# RWcircuit_2.net
KiCad netlist of a schematic drawn in Altium Designer
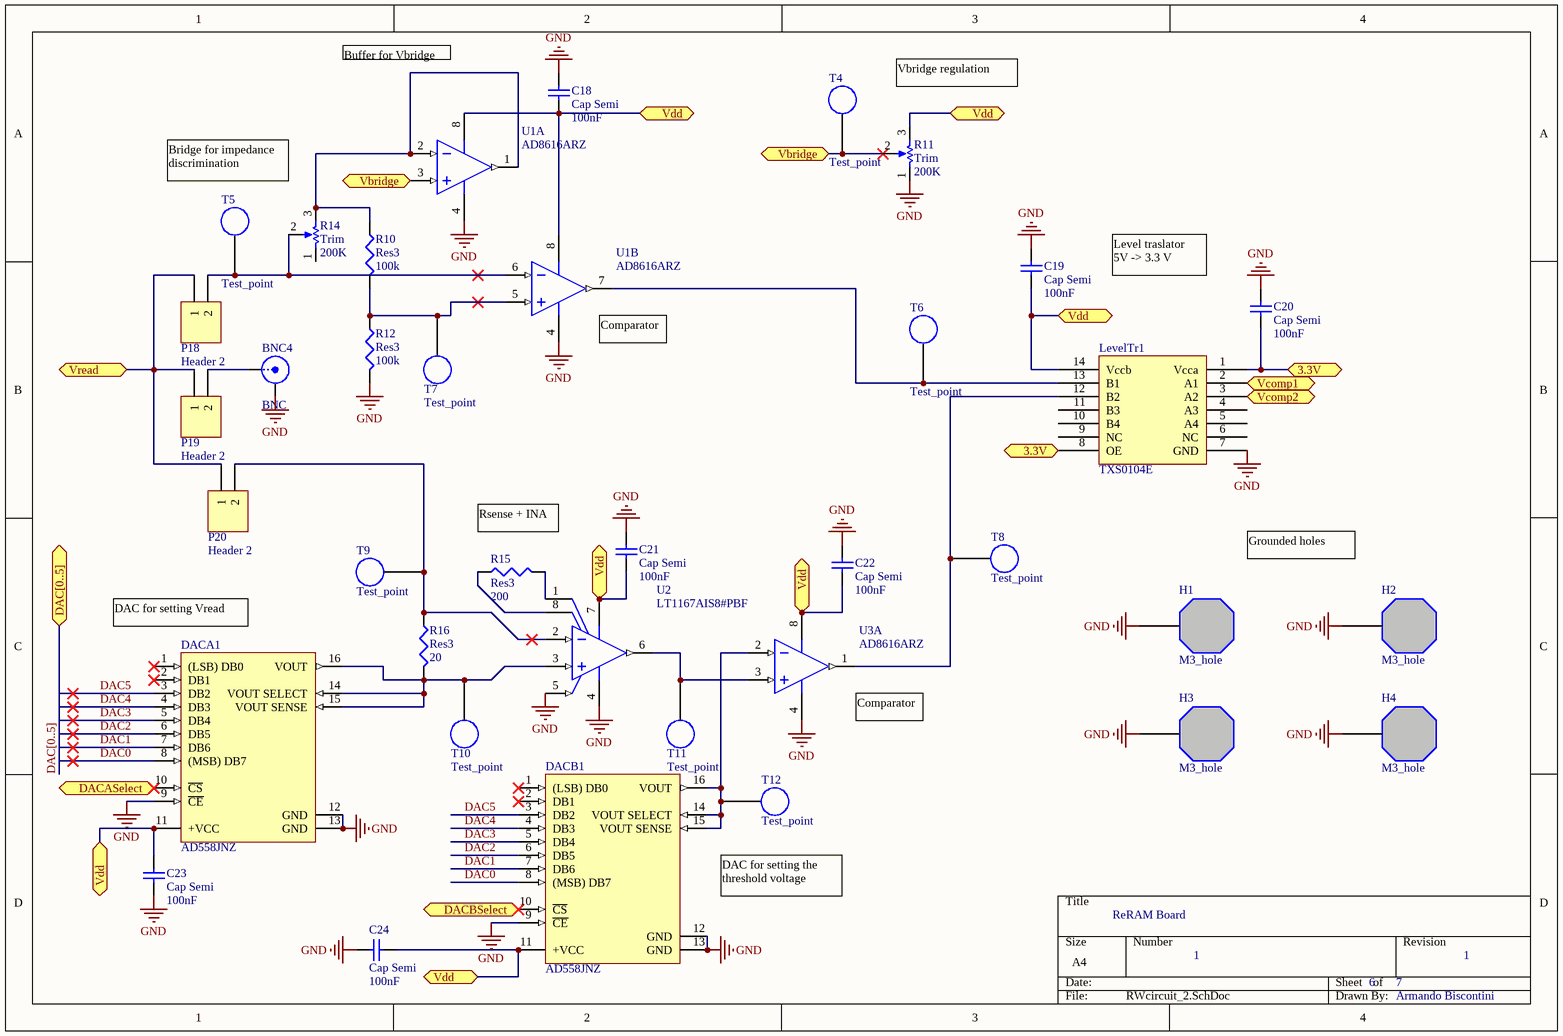
[diagram p0: RWcircuit_2.SchDoc]

(export (version "E")
  (design (tool "Eeschema 10.0.6"))
  (components
    (comp (ref "BNC4")
      (value "BNC")
      (footprint "BNC_RA CON")
      (description "BNC Elbow Connector")
      (fields (field (name "PUBLISHER") "Altium Limited"))
      (libsource (lib "Miscellaneous Connectors") (part "BNC"))
    )
    (comp (ref "C18")
      (value "Cap Semi")
      (footprint "C1206")
      (description "Capacitor (Semiconductor SIM Model)")
      (fields (field (name "ALTIUM_VALUE") "100nF") (field (name "PUBLISHER") "Altium Limited"))
      (libsource (lib "Miscellaneous Devices") (part "Cap Semi"))
    )
    (comp (ref "C19")
      (value "Cap Semi")
      (footprint "C1206")
      (description "Capacitor (Semiconductor SIM Model)")
      (fields (field (name "ALTIUM_VALUE") "100nF") (field (name "PUBLISHER") "Altium Limited"))
      (libsource (lib "Miscellaneous Devices") (part "Cap Semi"))
    )
    (comp (ref "C20")
      (value "Cap Semi")
      (footprint "C1206")
      (description "Capacitor (Semiconductor SIM Model)")
      (fields (field (name "ALTIUM_VALUE") "100nF") (field (name "PUBLISHER") "Altium Limited"))
      (libsource (lib "Miscellaneous Devices") (part "Cap Semi"))
    )
    (comp (ref "C21")
      (value "Cap Semi")
      (footprint "C1206")
      (description "Capacitor (Semiconductor SIM Model)")
      (fields (field (name "ALTIUM_VALUE") "100nF") (field (name "PUBLISHER") "Altium Limited"))
      (libsource (lib "Miscellaneous Devices") (part "Cap Semi"))
    )
    (comp (ref "C22")
      (value "Cap Semi")
      (footprint "C1206")
      (description "Capacitor (Semiconductor SIM Model)")
      (fields (field (name "ALTIUM_VALUE") "100nF") (field (name "PUBLISHER") "Altium Limited"))
      (libsource (lib "Miscellaneous Devices") (part "Cap Semi"))
    )
    (comp (ref "C23")
      (value "Cap Semi")
      (footprint "C1206")
      (description "Capacitor (Semiconductor SIM Model)")
      (fields (field (name "ALTIUM_VALUE") "100nF") (field (name "PUBLISHER") "Altium Limited"))
      (libsource (lib "Miscellaneous Devices") (part "Cap Semi"))
    )
    (comp (ref "C24")
      (value "Cap Semi")
      (footprint "C1206")
      (description "Capacitor (Semiconductor SIM Model)")
      (fields (field (name "ALTIUM_VALUE") "100nF") (field (name "PUBLISHER") "Altium Limited"))
      (libsource (lib "Miscellaneous Devices") (part "Cap Semi"))
    )
    (comp (ref "DACA1")
      (value "AD558JNZ")
      (footprint "N-16")
      (description "Single 8-Bit Low Cost Complete uP-Compatible DACPORT, 0 to +70 degC, N-16, Pb-Free, Tube")
      (fields (field (name "GENERIC PART NUMBER") "AD558") (field (name "MANUFACTURER") "Analog Devices"))
      (libsource (lib "Analog Devices Data Converters Digital-to-Analog Converters") (part "AD558JNZ"))
    )
    (comp (ref "DACB1")
      (value "AD558JNZ")
      (footprint "N-16")
      (description "Single 8-Bit Low Cost Complete uP-Compatible DACPORT, 0 to +70 degC, N-16, Pb-Free, Tube")
      (fields (field (name "GENERIC PART NUMBER") "AD558") (field (name "MANUFACTURER") "Analog Devices"))
      (libsource (lib "Analog Devices Data Converters Digital-to-Analog Converters") (part "AD558JNZ"))
    )
    (comp (ref "H1")
      (value "M3_hole")
      (footprint "M3_hole")
      (description "M3 hole")
      (libsource (lib "ReRAM_Board_library") (part "M3_hole"))
    )
    (comp (ref "H2")
      (value "M3_hole")
      (footprint "M3_hole")
      (description "M3 hole")
      (libsource (lib "ReRAM_Board_library") (part "M3_hole"))
    )
    (comp (ref "H3")
      (value "M3_hole")
      (footprint "M3_hole")
      (description "M3 hole")
      (libsource (lib "ReRAM_Board_library") (part "M3_hole"))
    )
    (comp (ref "H4")
      (value "M3_hole")
      (footprint "M3_hole")
      (description "M3 hole")
      (libsource (lib "ReRAM_Board_library") (part "M3_hole"))
    )
    (comp (ref "LevelTr1")
      (value "TXS0104E")
      (footprint "SOIC127P600X175-14N")
      (description "Texas Instruments TXS0104E")
      (libsource (lib "ReRAM_Board_library") (part "TXS0104E"))
    )
    (comp (ref "P18")
      (value "Header 2")
      (footprint "HDR1X2")
      (description "Header, 2-Pin")
      (fields (field (name "PUBLISHER") "Altium Limited"))
      (libsource (lib "Miscellaneous Connectors") (part "Header 2"))
    )
    (comp (ref "P19")
      (value "Header 2")
      (footprint "HDR1X2")
      (description "Header, 2-Pin")
      (fields (field (name "PUBLISHER") "Altium Limited"))
      (libsource (lib "Miscellaneous Connectors") (part "Header 2"))
    )
    (comp (ref "P20")
      (value "Header 2")
      (footprint "HDR1X2")
      (description "Header, 2-Pin")
      (fields (field (name "PUBLISHER") "Altium Limited"))
      (libsource (lib "Miscellaneous Connectors") (part "Header 2"))
    )
    (comp (ref "R10")
      (value "Res3")
      (footprint "J1-0603")
      (description "Resistor")
      (fields (field (name "ALTIUM_VALUE") "100k") (field (name "PUBLISHER") "Altium Limited"))
      (libsource (lib "Miscellaneous Devices") (part "Res3"))
    )
    (comp (ref "R11")
      (value "Trim")
      (footprint "Trim_Bourns_3266W")
      (description "Trimmer Bourns 3266W")
      (fields (field (name "ALTIUM_VALUE") "200K") (field (name "PUBLISHER") "Altium Limited"))
      (libsource (lib "ReRAM_Board_library") (part "Trim_Bourns_3266W"))
    )
    (comp (ref "R12")
      (value "Res3")
      (footprint "J1-0603")
      (description "Resistor")
      (fields (field (name "ALTIUM_VALUE") "100k") (field (name "PUBLISHER") "Altium Limited"))
      (libsource (lib "Miscellaneous Devices") (part "Res3"))
    )
    (comp (ref "R14")
      (value "Trim")
      (footprint "Trim_Bourns_3266W")
      (description "Trimmer Bourns 3266W")
      (fields (field (name "ALTIUM_VALUE") "200K") (field (name "PUBLISHER") "Altium Limited"))
      (libsource (lib "ReRAM_Board_library") (part "Trim_Bourns_3266W"))
    )
    (comp (ref "R15")
      (value "Res3")
      (footprint "J1-0603")
      (description "Resistor")
      (fields (field (name "ALTIUM_VALUE") "200") (field (name "PUBLISHER") "Altium Limited"))
      (libsource (lib "Miscellaneous Devices") (part "Res3"))
    )
    (comp (ref "R16")
      (value "Res3")
      (footprint "J1-0603")
      (description "Resistor")
      (fields (field (name "ALTIUM_VALUE") "20") (field (name "PUBLISHER") "Altium Limited"))
      (libsource (lib "Miscellaneous Devices") (part "Res3"))
    )
    (comp (ref "T4")
      (value "Test_point")
      (footprint "Test_point_1.32mm")
      (description "Test point 1.32mm")
      (libsource (lib "ReRAM_Board_library") (part "Test_point_1.32mm"))
    )
    (comp (ref "T5")
      (value "Test_point")
      (footprint "Test_point_1.32mm")
      (description "Test point 1.32mm")
      (libsource (lib "ReRAM_Board_library") (part "Test_point_1.32mm"))
    )
    (comp (ref "T6")
      (value "Test_point")
      (footprint "Test_point_1.32mm")
      (description "Test point 1.32mm")
      (libsource (lib "ReRAM_Board_library") (part "Test_point_1.32mm"))
    )
    (comp (ref "T7")
      (value "Test_point")
      (footprint "Test_point_1.32mm")
      (description "Test point 1.32mm")
      (libsource (lib "ReRAM_Board_library") (part "Test_point_1.32mm"))
    )
    (comp (ref "T8")
      (value "Test_point")
      (footprint "Test_point_1.32mm")
      (description "Test point 1.32mm")
      (libsource (lib "ReRAM_Board_library") (part "Test_point_1.32mm"))
    )
    (comp (ref "T9")
      (value "Test_point")
      (footprint "Test_point_1.32mm")
      (description "Test point 1.32mm")
      (libsource (lib "ReRAM_Board_library") (part "Test_point_1.32mm"))
    )
    (comp (ref "T10")
      (value "Test_point")
      (footprint "Test_point_1.32mm")
      (description "Test point 1.32mm")
      (libsource (lib "ReRAM_Board_library") (part "Test_point_1.32mm"))
    )
    (comp (ref "T11")
      (value "Test_point")
      (footprint "Test_point_1.32mm")
      (description "Test point 1.32mm")
      (libsource (lib "ReRAM_Board_library") (part "Test_point_1.32mm"))
    )
    (comp (ref "T12")
      (value "Test_point")
      (footprint "Test_point_1.32mm")
      (description "Test point 1.32mm")
      (libsource (lib "ReRAM_Board_library") (part "Test_point_1.32mm"))
    )
    (comp (ref "U1")
      (value "AD8616ARZ")
      (footprint "ADI-R-8_N")
      (fields (field (name "GENERIC PART NUMBER") "AD8616") (field (name "MANUFACTURER") "Analog Devices"))
      (libsource (lib "Analog Devices Operational Amplifiers") (part "AD8616ARZ"))
    )
    (comp (ref "U2")
      (value "LT1167AIS8#PBF")
      (footprint "LT-S8-8_N")
      (fields
        (field (name "LINEAR TECHNOLOGY PART NUMBER") "LT1167")
        (field (name "MANUFACTURER") "Linear Technology")
      )
      (libsource (lib "Linear Technology Operational Amplifiers (LT1000)") (part "LT1167AIS8#PBF"))
    )
    (comp (ref "U3")
      (value "AD8616ARZ")
      (footprint "ADI-R-8_N")
      (fields (field (name "GENERIC PART NUMBER") "AD8616") (field (name "MANUFACTURER") "Analog Devices"))
      (libsource (lib "Analog Devices Operational Amplifiers") (part "AD8616ARZ"))
    )
  )
  (nets
    (net (code "1") (name "/3.3V") (class "Default")
      (node (ref "C20") (pin "2") (pinfunction "2_2") (pintype "passive"))
      (node (ref "LevelTr1") (pin "1") (pinfunction "Vcca_1") (pintype "passive"))
      (node (ref "LevelTr1") (pin "8") (pinfunction "OE_8") (pintype "passive"))
    )
    (net (code "2") (name "/DAC0") (class "Default")
      (node (ref "DACA1") (pin "8") (pinfunction "(MSB)_DB7_8") (pintype "input"))
      (node (ref "DACB1") (pin "8") (pinfunction "(MSB)_DB7_8") (pintype "input"))
    )
    (net (code "3") (name "/DAC1") (class "Default")
      (node (ref "DACA1") (pin "7") (pinfunction "DB6_7") (pintype "input"))
      (node (ref "DACB1") (pin "7") (pinfunction "DB6_7") (pintype "input"))
    )
    (net (code "4") (name "/DAC2") (class "Default")
      (node (ref "DACA1") (pin "6") (pinfunction "DB5_6") (pintype "input"))
      (node (ref "DACB1") (pin "6") (pinfunction "DB5_6") (pintype "input"))
    )
    (net (code "5") (name "/DAC3") (class "Default")
      (node (ref "DACA1") (pin "5") (pinfunction "DB4_5") (pintype "input"))
      (node (ref "DACB1") (pin "5") (pinfunction "DB4_5") (pintype "input"))
    )
    (net (code "6") (name "/DAC4") (class "Default")
      (node (ref "DACA1") (pin "4") (pinfunction "DB3_4") (pintype "input"))
      (node (ref "DACB1") (pin "4") (pinfunction "DB3_4") (pintype "input"))
    )
    (net (code "7") (name "/DAC5") (class "Default")
      (node (ref "DACA1") (pin "3") (pinfunction "DB2_3") (pintype "input"))
      (node (ref "DACB1") (pin "3") (pinfunction "DB2_3") (pintype "input"))
    )
    (net (code "8") (name "/DACASelect") (class "Default")
      (node (ref "DACA1") (pin "10") (pinfunction "~{CS}_10") (pintype "input+no_connect"))
    )
    (net (code "9") (name "/DACBSelect") (class "Default")
      (node (ref "DACB1") (pin "10") (pinfunction "~{CS}_10") (pintype "input+no_connect"))
    )
    (net (code "11") (name "/Vbridge") (class "Default")
      (node (ref "R11") (pin "2") (pinfunction "TAP_2") (pintype "passive"))
      (node (ref "T4") (pin "1") (pintype "passive"))
      (node (ref "U1") (pin "3") (pinfunction "+IN_A_3") (pintype "input"))
    )
    (net (code "12") (name "/Vcomp1") (class "Default")
      (node (ref "LevelTr1") (pin "2") (pinfunction "A1_2") (pintype "passive"))
    )
    (net (code "13") (name "/Vcomp2") (class "Default")
      (node (ref "LevelTr1") (pin "3") (pinfunction "A2_3") (pintype "passive"))
    )
    (net (code "14") (name "/Vdd") (class "Default")
      (node (ref "C18") (pin "2") (pinfunction "2_2") (pintype "passive"))
      (node (ref "C19") (pin "2") (pinfunction "2_2") (pintype "passive"))
      (node (ref "C21") (pin "1") (pinfunction "1_1") (pintype "passive"))
      (node (ref "C22") (pin "2") (pinfunction "2_2") (pintype "passive"))
      (node (ref "C23") (pin "1") (pinfunction "1_1") (pintype "passive"))
      (node (ref "C24") (pin "2") (pinfunction "2_2") (pintype "passive"))
      (node (ref "DACA1") (pin "11") (pinfunction "+VCC_11") (pintype "power_in"))
      (node (ref "DACB1") (pin "11") (pinfunction "+VCC_11") (pintype "power_in"))
      (node (ref "LevelTr1") (pin "14") (pinfunction "Vccb_14") (pintype "passive"))
      (node (ref "R11") (pin "3") (pinfunction "BOT_3") (pintype "passive"))
      (node (ref "U1") (pin "8") (pinfunction "+V_8") (pintype "power_in"))
      (node (ref "U2") (pin "7") (pinfunction "+VS_7") (pintype "power_in"))
      (node (ref "U3") (pin "8") (pinfunction "+V_8") (pintype "power_in"))
    )
    (net (code "15") (name "/Vread") (class "Default")
      (node (ref "P18") (pin "1") (pinfunction "1_1") (pintype "passive"))
      (node (ref "P19") (pin "1") (pinfunction "1_1") (pintype "passive"))
      (node (ref "P20") (pin "1") (pinfunction "1_1") (pintype "passive"))
    )
    (net (code "16") (name "GND") (class "Default")
      (node (ref "BNC4") (pin "2") (pinfunction "Y_2") (pintype "passive"))
      (node (ref "C18") (pin "1") (pinfunction "1_1") (pintype "passive"))
      (node (ref "C19") (pin "1") (pinfunction "1_1") (pintype "passive"))
      (node (ref "C20") (pin "1") (pinfunction "1_1") (pintype "passive"))
      (node (ref "C21") (pin "2") (pinfunction "2_2") (pintype "passive"))
      (node (ref "C22") (pin "1") (pinfunction "1_1") (pintype "passive"))
      (node (ref "C23") (pin "2") (pinfunction "2_2") (pintype "passive"))
      (node (ref "C24") (pin "1") (pinfunction "1_1") (pintype "passive"))
      (node (ref "DACA1") (pin "12") (pinfunction "GND_12") (pintype "power_in"))
      (node (ref "DACA1") (pin "13") (pinfunction "GND_13") (pintype "power_in"))
      (node (ref "DACA1") (pin "9") (pinfunction "~{CE}_9") (pintype "input"))
      (node (ref "DACB1") (pin "12") (pinfunction "GND_12") (pintype "power_in"))
      (node (ref "DACB1") (pin "13") (pinfunction "GND_13") (pintype "power_in"))
      (node (ref "DACB1") (pin "9") (pinfunction "~{CE}_9") (pintype "input"))
      (node (ref "H1") (pin "1") (pintype "passive"))
      (node (ref "H2") (pin "1") (pintype "passive"))
      (node (ref "H3") (pin "1") (pintype "passive"))
      (node (ref "H4") (pin "1") (pintype "passive"))
      (node (ref "LevelTr1") (pin "7") (pinfunction "GND_7") (pintype "passive"))
      (node (ref "R11") (pin "1") (pinfunction "TOP_1") (pintype "passive"))
      (node (ref "R12") (pin "1") (pinfunction "1_1") (pintype "passive"))
      (node (ref "U1") (pin "4") (pinfunction "-V_4") (pintype "power_in"))
      (node (ref "U2") (pin "4") (pinfunction "-VS_4") (pintype "power_in"))
      (node (ref "U2") (pin "5") (pinfunction "REF_5") (pintype "input"))
      (node (ref "U3") (pin "4") (pinfunction "-V_4") (pintype "power_in"))
    )
    (net (code "17") (name "Net-(BNC4-X)") (class "Default")
      (node (ref "BNC4") (pin "1") (pinfunction "X_1") (pintype "passive"))
      (node (ref "P19") (pin "2") (pinfunction "2_2") (pintype "passive"))
    )
    (net (code "18") (name "Net-(DACA1-VOUT)") (class "Default")
      (node (ref "DACA1") (pin "14") (pinfunction "VOUT_SELECT_14") (pintype "input"))
      (node (ref "DACA1") (pin "15") (pinfunction "VOUT_SENSE_15") (pintype "input"))
      (node (ref "DACA1") (pin "16") (pinfunction "VOUT_16") (pintype "output"))
      (node (ref "R16") (pin "1") (pinfunction "1_1") (pintype "passive"))
      (node (ref "T10") (pin "1") (pintype "passive"))
      (node (ref "U2") (pin "3") (pinfunction "+IN_3") (pintype "input"))
    )
    (net (code "19") (name "Net-(DACB1-VOUT)") (class "Default")
      (node (ref "DACB1") (pin "14") (pinfunction "VOUT_SELECT_14") (pintype "input"))
      (node (ref "DACB1") (pin "15") (pinfunction "VOUT_SENSE_15") (pintype "input"))
      (node (ref "DACB1") (pin "16") (pinfunction "VOUT_16") (pintype "output"))
      (node (ref "T12") (pin "1") (pintype "passive"))
      (node (ref "U3") (pin "2") (pinfunction "-IN_A_2") (pintype "input"))
    )
    (net (code "20") (name "Net-(LevelTr1-B1)") (class "Default")
      (node (ref "LevelTr1") (pin "13") (pinfunction "B1_13") (pintype "passive"))
      (node (ref "T6") (pin "1") (pintype "passive"))
      (node (ref "U1") (pin "7") (pinfunction "OUT_B_7") (pintype "output"))
    )
    (net (code "21") (name "Net-(LevelTr1-B2)") (class "Default")
      (node (ref "LevelTr1") (pin "12") (pinfunction "B2_12") (pintype "passive"))
      (node (ref "T8") (pin "1") (pintype "passive"))
      (node (ref "U3") (pin "1") (pinfunction "OUT_A_1") (pintype "output"))
    )
    (net (code "22") (name "Net-(R14-BOT)") (class "Default")
      (node (ref "R10") (pin "2") (pinfunction "2_2") (pintype "passive"))
      (node (ref "R14") (pin "3") (pinfunction "BOT_3") (pintype "passive"))
      (node (ref "U1") (pin "1") (pinfunction "OUT_A_1") (pintype "output"))
      (node (ref "U1") (pin "2") (pinfunction "-IN_A_2") (pintype "input"))
    )
    (net (code "23") (name "Net-(R14-TAP)") (class "Default")
      (node (ref "P18") (pin "2") (pinfunction "2_2") (pintype "passive"))
      (node (ref "R14") (pin "2") (pinfunction "TAP_2") (pintype "passive"))
      (node (ref "T5") (pin "1") (pintype "passive"))
      (node (ref "U1") (pin "6") (pinfunction "-IN_B_6") (pintype "input"))
    )
    (net (code "24") (name "Net-(R15-Pad1)") (class "Default")
      (node (ref "R15") (pin "1") (pinfunction "1_1") (pintype "passive"))
      (node (ref "U2") (pin "1") (pinfunction "RG_1") (pintype "passive"))
    )
    (net (code "25") (name "Net-(R15-Pad2)") (class "Default")
      (node (ref "R15") (pin "2") (pinfunction "2_2") (pintype "passive"))
      (node (ref "U2") (pin "8") (pinfunction "RG_8") (pintype "passive"))
    )
    (net (code "26") (name "Net-(U1B-+IN_B)") (class "Default")
      (node (ref "R10") (pin "1") (pinfunction "1_1") (pintype "passive"))
      (node (ref "R12") (pin "2") (pinfunction "2_2") (pintype "passive"))
      (node (ref "T7") (pin "1") (pintype "passive"))
      (node (ref "U1") (pin "5") (pinfunction "+IN_B_5") (pintype "input"))
    )
    (net (code "27") (name "Net-(U2--IN)") (class "Default")
      (node (ref "P20") (pin "2") (pinfunction "2_2") (pintype "passive"))
      (node (ref "R16") (pin "2") (pinfunction "2_2") (pintype "passive"))
      (node (ref "T9") (pin "1") (pintype "passive"))
      (node (ref "U2") (pin "2") (pinfunction "-IN_2") (pintype "input"))
    )
    (net (code "28") (name "Net-(U2-OUTPUT)") (class "Default")
      (node (ref "T11") (pin "1") (pintype "passive"))
      (node (ref "U2") (pin "6") (pinfunction "OUTPUT_6") (pintype "output"))
      (node (ref "U3") (pin "3") (pinfunction "+IN_A_3") (pintype "input"))
    )
    (net (code "29") (name "unconnected-(DACA1-(LSB)_DB0-Pad1)") (class "Default")
      (node (ref "DACA1") (pin "1") (pinfunction "(LSB)_DB0_1") (pintype "input+no_connect"))
    )
    (net (code "30") (name "unconnected-(DACA1-DB1-Pad2)") (class "Default")
      (node (ref "DACA1") (pin "2") (pinfunction "DB1_2") (pintype "input+no_connect"))
    )
    (net (code "31") (name "unconnected-(DACB1-(LSB)_DB0-Pad1)") (class "Default")
      (node (ref "DACB1") (pin "1") (pinfunction "(LSB)_DB0_1") (pintype "input+no_connect"))
    )
    (net (code "32") (name "unconnected-(DACB1-DB1-Pad2)") (class "Default")
      (node (ref "DACB1") (pin "2") (pinfunction "DB1_2") (pintype "input+no_connect"))
    )
    (net (code "33") (name "unconnected-(LevelTr1-A3-Pad4)") (class "Default")
      (node (ref "LevelTr1") (pin "4") (pinfunction "A3_4") (pintype "passive"))
    )
    (net (code "34") (name "unconnected-(LevelTr1-A4-Pad5)") (class "Default")
      (node (ref "LevelTr1") (pin "5") (pinfunction "A4_5") (pintype "passive"))
    )
    (net (code "35") (name "unconnected-(LevelTr1-B3-Pad11)") (class "Default")
      (node (ref "LevelTr1") (pin "11") (pinfunction "B3_11") (pintype "passive"))
    )
    (net (code "36") (name "unconnected-(LevelTr1-B4-Pad10)") (class "Default")
      (node (ref "LevelTr1") (pin "10") (pinfunction "B4_10") (pintype "passive"))
    )
    (net (code "37") (name "unconnected-(LevelTr1-NC-Pad6)") (class "Default")
      (node (ref "LevelTr1") (pin "6") (pinfunction "NC_6") (pintype "passive"))
    )
    (net (code "38") (name "unconnected-(LevelTr1-NC-Pad9)") (class "Default")
      (node (ref "LevelTr1") (pin "9") (pinfunction "NC_9") (pintype "passive"))
    )
    (net (code "39") (name "unconnected-(R14-TOP-Pad1)") (class "Default")
      (node (ref "R14") (pin "1") (pinfunction "TOP_1") (pintype "passive"))
    )
  )
)
